# Fonte12V.net
KiCad netlist of a schematic drawn in EAGLE
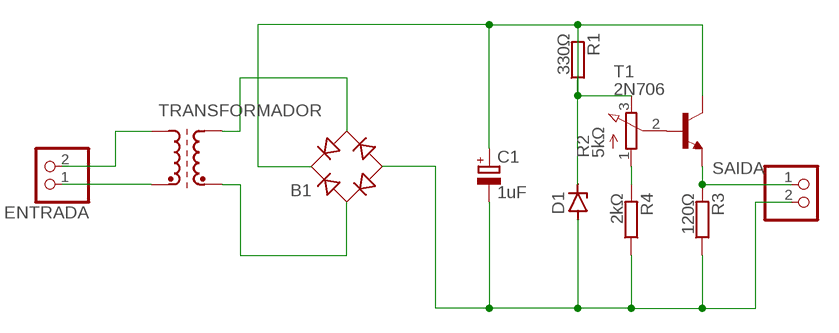
[diagram p0: schematic, sheet 1]

(export (version "E")
  (design (tool "Eeschema 10.0.6"))
  (components
    (comp (ref "B1")
      (value "RB1A")
      (footprint "eagle-import:RB1A")
      (libsource (lib "eagle-import") (part "RB1A"))
    )
    (comp (ref "C1")
      (value "1uF")
      (footprint "eagle-import:E2,5-6E")
      (libsource (lib "eagle-import") (part "CPOL-EUE2,5-6E"))
    )
    (comp (ref "D1")
      (value "ZENER-DIODEDO41Z10")
      (footprint "eagle-import:DO41Z10")
      (libsource (lib "eagle-import") (part "ZENER-DIODEDO41Z10"))
    )
    (comp (ref "ENTRADA")
      (value "PINHD-1X2")
      (footprint "eagle-import:1X02")
      (libsource (lib "eagle-import") (part "PINHD-1X2"))
    )
    (comp (ref "R1")
      (value "330Ω")
      (footprint "eagle-import:BVS")
      (libsource (lib "eagle-import") (part "BVS"))
    )
    (comp (ref "R2")
      (value "5kΩ")
      (footprint "eagle-import:3RP_1610N")
      (libsource (lib "eagle-import") (part "3RP/1610N"))
    )
    (comp (ref "R3")
      (value "120Ω")
      (footprint "eagle-import:BVS")
      (libsource (lib "eagle-import") (part "BVS"))
    )
    (comp (ref "R4")
      (value "2kΩ")
      (footprint "eagle-import:BVS")
      (libsource (lib "eagle-import") (part "BVS"))
    )
    (comp (ref "SAIDA")
      (value "PINHD-1X2")
      (footprint "eagle-import:1X02")
      (libsource (lib "eagle-import") (part "PINHD-1X2"))
    )
    (comp (ref "T1")
      (value "2N706")
      (footprint "eagle-import:TO18")
      (libsource (lib "eagle-import") (part "2N706"))
    )
    (comp (ref "TRANSFORMADOR")
      (value "SM-T4")
      (footprint "eagle-import:SM-T4")
      (libsource (lib "eagle-import") (part "SM-T4"))
    )
  )
  (nets
    (net (code "1") (name "Net-(B1-Pad-)") (class "Default")
      (node (ref "B1") (pin "-") (pinfunction "-_-") (pintype "passive"))
      (node (ref "C1") (pin "-") (pinfunction "-_-") (pintype "passive"))
      (node (ref "D1") (pin "A") (pinfunction "A_A") (pintype "passive"))
      (node (ref "R3") (pin "1") (pinfunction "1_1") (pintype "passive"))
      (node (ref "R4") (pin "1") (pinfunction "1_1") (pintype "passive"))
      (node (ref "SAIDA") (pin "2") (pinfunction "2_2") (pintype "passive"))
    )
    (net (code "2") (name "Net-(R2-A)") (class "Default")
      (node (ref "R2") (pin "1") (pinfunction "A_1") (pintype "passive"))
      (node (ref "R4") (pin "2") (pinfunction "2_2") (pintype "passive"))
    )
    (net (code "3") (name "Net-(R2-E)") (class "Default")
      (node (ref "B1") (pin "+") (pinfunction "+_+") (pintype "passive"))
      (node (ref "C1") (pin "+") (pinfunction "+_+") (pintype "passive"))
      (node (ref "D1") (pin "C") (pinfunction "C_C") (pintype "passive"))
      (node (ref "R1") (pin "1") (pinfunction "1_1") (pintype "passive"))
      (node (ref "R1") (pin "2") (pinfunction "2_2") (pintype "passive"))
      (node (ref "R2") (pin "3") (pinfunction "E_3") (pintype "passive"))
      (node (ref "T1") (pin "3") (pinfunction "C_3") (pintype "passive"))
    )
    (net (code "4") (name "Net-(R2-S)") (class "Default")
      (node (ref "R2") (pin "2") (pinfunction "S_2") (pintype "passive"))
      (node (ref "T1") (pin "2") (pinfunction "B_2") (pintype "passive"))
    )
    (net (code "5") (name "Net-(T1-E)") (class "Default")
      (node (ref "R3") (pin "2") (pinfunction "2_2") (pintype "passive"))
      (node (ref "SAIDA") (pin "1") (pinfunction "1_1") (pintype "passive"))
      (node (ref "T1") (pin "1") (pinfunction "E_1") (pintype "passive"))
    )
    (net (code "6") (name "Net-(TRANSFORMADOR-A1)") (class "Default")
      (node (ref "ENTRADA") (pin "2") (pinfunction "2_2") (pintype "passive"))
      (node (ref "TRANSFORMADOR") (pin "1") (pinfunction "A1_1") (pintype "passive"))
    )
    (net (code "7") (name "Net-(TRANSFORMADOR-A2)") (class "Default")
      (node (ref "B1") (pin "AC2") (pinfunction "AC2_AC2") (pintype "passive"))
      (node (ref "TRANSFORMADOR") (pin "5") (pinfunction "A2_5") (pintype "passive"))
    )
    (net (code "8") (name "Net-(TRANSFORMADOR-E1)") (class "Default")
      (node (ref "ENTRADA") (pin "1") (pinfunction "1_1") (pintype "passive"))
      (node (ref "TRANSFORMADOR") (pin "2") (pinfunction "E1_2") (pintype "passive"))
    )
    (net (code "9") (name "Net-(TRANSFORMADOR-E2)") (class "Default")
      (node (ref "B1") (pin "AC1") (pinfunction "AC1_AC1") (pintype "passive"))
      (node (ref "TRANSFORMADOR") (pin "4") (pinfunction "E2_4") (pintype "passive"))
    )
  )
)
